# Actuators.net
KiCad netlist of a schematic drawn in Altium Designer
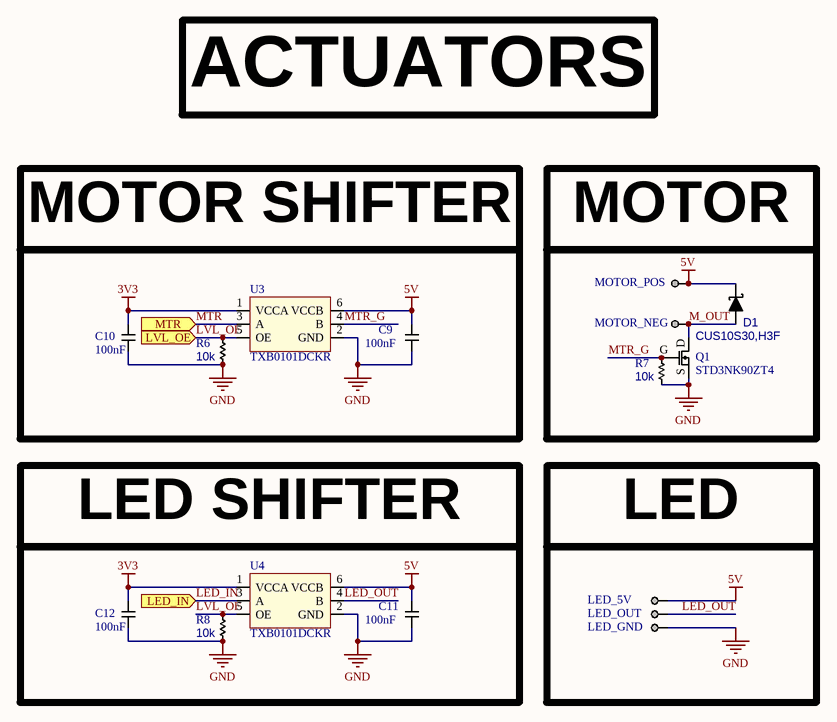
[diagram p0: Actuators.SchDoc]

(export (version "E")
  (design (tool "Eeschema 10.0.6"))
  (components
    (comp (ref "C9")
      (value "100nF")
      (footprint "CAP_0402_HIGH")
      (description "0402 Capacitor")
      (libsource (lib "smLib") (part "Capacitor_0402"))
    )
    (comp (ref "C10")
      (value "100nF")
      (footprint "CAP_0402_HIGH")
      (description "0402 Capacitor")
      (libsource (lib "smLib") (part "Capacitor_0402"))
    )
    (comp (ref "C11")
      (value "100nF")
      (footprint "CAP_0402_HIGH")
      (description "0402 Capacitor")
      (libsource (lib "smLib") (part "Capacitor_0402"))
    )
    (comp (ref "C12")
      (value "100nF")
      (footprint "CAP_0402_HIGH")
      (description "0402 Capacitor")
      (libsource (lib "smLib") (part "Capacitor_0402"))
    )
    (comp (ref "D1")
      (value "CUS10S30,H3F")
      (footprint "CUS10S30,H3F")
      (description "CUS10S30,H3F Diode Schottky 30V 1A Surface Mount USC")
      (libsource (lib "smLib") (part "CUS10S30,H3F"))
    )
    (comp (ref "LED_5V")
      (value "18 AWG Hole")
      (footprint "18 AWG Hole")
      (libsource (lib "smLib") (part "18 AWG Hole"))
    )
    (comp (ref "LED_GND")
      (value "18 AWG Hole")
      (footprint "18 AWG Hole")
      (libsource (lib "smLib") (part "18 AWG Hole"))
    )
    (comp (ref "LED_OUT")
      (value "18 AWG Hole")
      (footprint "18 AWG Hole")
      (libsource (lib "smLib") (part "18 AWG Hole"))
    )
    (comp (ref "MOTOR_NEG")
      (value "18 AWG Hole")
      (footprint "18 AWG Hole")
      (libsource (lib "smLib") (part "18 AWG Hole"))
    )
    (comp (ref "MOTOR_POS")
      (value "18 AWG Hole")
      (footprint "18 AWG Hole")
      (libsource (lib "smLib") (part "18 AWG Hole"))
    )
    (comp (ref "Q1")
      (value "STD3NK90ZT4")
      (footprint "STD3NK90ZT4")
      (description "STD3NK90ZT4 N-Channel 900 V 3A (Tc) 90W (Tc) Surface Mount DPAK")
      (libsource (lib "smLib") (part "STD3NK90ZT4"))
    )
    (comp (ref "R6")
      (value "10k")
      (footprint "RES_0402_HIGH")
      (description "0402 Resistor")
      (libsource (lib "smLib") (part "Resistor_0402"))
    )
    (comp (ref "R7")
      (value "10k")
      (footprint "RES_0402_HIGH")
      (description "0402 Resistor")
      (libsource (lib "smLib") (part "Resistor_0402"))
    )
    (comp (ref "R8")
      (value "10k")
      (footprint "RES_0402_HIGH")
      (description "0402 Resistor")
      (libsource (lib "smLib") (part "Resistor_0402"))
    )
    (comp (ref "U3")
      (value "TXB0101DCKR")
      (footprint "TXB0101DCKR")
      (description "TXB0101DCKR Voltage Level Translator Bidirectional 1 Circuit 1 Channel 100Mbps SC-70-6")
      (libsource (lib "smLib") (part "TXB0101DCKR"))
    )
    (comp (ref "U4")
      (value "TXB0101DCKR")
      (footprint "TXB0101DCKR")
      (description "TXB0101DCKR Voltage Level Translator Bidirectional 1 Circuit 1 Channel 100Mbps SC-70-6")
      (libsource (lib "smLib") (part "TXB0101DCKR"))
    )
  )
  (nets
    (net (code "1") (name "/LED_IN") (class "Default")
      (node (ref "U4") (pin "3") (pinfunction "A_3") (pintype "passive"))
    )
    (net (code "2") (name "/LED_OUT") (class "Default")
      (node (ref "LED_OUT") (pin "1") (pinfunction "1_1") (pintype "passive"))
      (node (ref "U4") (pin "4") (pinfunction "B_4") (pintype "passive"))
    )
    (net (code "3") (name "/LVL_OE") (class "Default")
      (node (ref "R6") (pin "2") (pinfunction "2_2") (pintype "passive"))
      (node (ref "R8") (pin "2") (pinfunction "2_2") (pintype "passive"))
      (node (ref "U3") (pin "5") (pinfunction "OE_5") (pintype "passive"))
      (node (ref "U4") (pin "5") (pinfunction "OE_5") (pintype "passive"))
    )
    (net (code "4") (name "/MTR") (class "Default")
      (node (ref "U3") (pin "3") (pinfunction "A_3") (pintype "passive"))
    )
    (net (code "5") (name "/MTR_G") (class "Default")
      (node (ref "Q1") (pin "G") (pinfunction "G_G") (pintype "passive"))
      (node (ref "R7") (pin "2") (pinfunction "2_2") (pintype "passive"))
      (node (ref "U3") (pin "4") (pinfunction "B_4") (pintype "passive"))
    )
    (net (code "6") (name "/M_OUT") (class "Default")
      (node (ref "D1") (pin "2") (pinfunction "2_2") (pintype "passive"))
      (node (ref "MOTOR_NEG") (pin "1") (pinfunction "1_1") (pintype "passive"))
      (node (ref "Q1") (pin "D") (pinfunction "D_D") (pintype "passive"))
    )
    (net (code "7") (name "3V3") (class "Default")
      (node (ref "C10") (pin "2") (pinfunction "2_2") (pintype "passive"))
      (node (ref "C12") (pin "2") (pinfunction "2_2") (pintype "passive"))
      (node (ref "U3") (pin "1") (pinfunction "VCCA_1") (pintype "passive"))
      (node (ref "U4") (pin "1") (pinfunction "VCCA_1") (pintype "passive"))
    )
    (net (code "8") (name "5V") (class "Default")
      (node (ref "C11") (pin "2") (pinfunction "2_2") (pintype "passive"))
      (node (ref "C9") (pin "2") (pinfunction "2_2") (pintype "passive"))
      (node (ref "D1") (pin "1") (pinfunction "1_1") (pintype "passive"))
      (node (ref "LED_5V") (pin "1") (pinfunction "1_1") (pintype "passive"))
      (node (ref "MOTOR_POS") (pin "1") (pinfunction "1_1") (pintype "passive"))
      (node (ref "U3") (pin "6") (pinfunction "VCCB_6") (pintype "passive"))
      (node (ref "U4") (pin "6") (pinfunction "VCCB_6") (pintype "passive"))
    )
    (net (code "9") (name "GND") (class "Default")
      (node (ref "C10") (pin "1") (pinfunction "1_1") (pintype "passive"))
      (node (ref "C11") (pin "1") (pinfunction "1_1") (pintype "passive"))
      (node (ref "C12") (pin "1") (pinfunction "1_1") (pintype "passive"))
      (node (ref "C9") (pin "1") (pinfunction "1_1") (pintype "passive"))
      (node (ref "LED_GND") (pin "1") (pinfunction "1_1") (pintype "passive"))
      (node (ref "Q1") (pin "S") (pinfunction "S_S") (pintype "passive"))
      (node (ref "R6") (pin "1") (pinfunction "1_1") (pintype "passive"))
      (node (ref "R7") (pin "1") (pinfunction "1_1") (pintype "passive"))
      (node (ref "R8") (pin "1") (pinfunction "1_1") (pintype "passive"))
      (node (ref "U3") (pin "2") (pinfunction "GND_2") (pintype "passive"))
      (node (ref "U4") (pin "2") (pinfunction "GND_2") (pintype "passive"))
    )
  )
)
